# connectors.net
KiCad netlist of a schematic drawn in Altium Designer
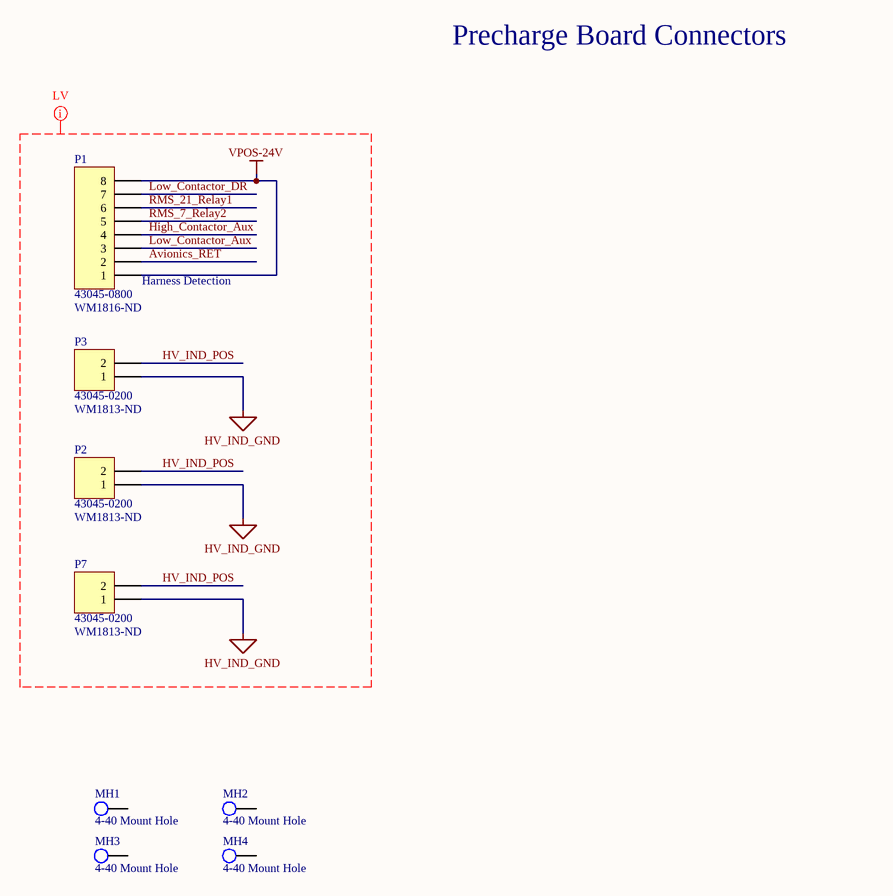
[diagram p0: connectors.SchDoc]

(export (version "E")
  (design (tool "Eeschema 10.0.6"))
  (components
    (comp (ref "MH1")
      (value "4-40 Mount Hole")
      (footprint "MH")
      (libsource (lib "misc") (part "4-40 Mount Hole"))
    )
    (comp (ref "MH2")
      (value "4-40 Mount Hole")
      (footprint "MH")
      (libsource (lib "misc") (part "4-40 Mount Hole"))
    )
    (comp (ref "MH3")
      (value "4-40 Mount Hole")
      (footprint "MH")
      (libsource (lib "misc") (part "4-40 Mount Hole"))
    )
    (comp (ref "MH4")
      (value "4-40 Mount Hole")
      (footprint "MH")
      (libsource (lib "misc") (part "4-40 Mount Hole"))
    )
    (comp (ref "P1")
      (value "43045-0800")
      (footprint "430450800")
      (description "CONN HEADER R/A 8POS 3MM")
      (fields (field (name "MANUFACTURER") "Molex") (field (name "SUPPLIER PART NUMBER 1") "WM1816-ND"))
      (libsource (lib "connector") (part "43045-0800"))
    )
    (comp (ref "P2")
      (value "43045-0200")
      (footprint "430450200")
      (description "CONN HEADER R/A 2POS")
      (fields (field (name "MANUFACTURER") "Molex") (field (name "SUPPLIER PART NUMBER 1") "WM1813-ND"))
      (libsource (lib "connector") (part "43045-0200"))
    )
    (comp (ref "P3")
      (value "43045-0200")
      (footprint "430450200")
      (description "CONN HEADER R/A 2POS")
      (fields (field (name "MANUFACTURER") "Molex") (field (name "SUPPLIER PART NUMBER 1") "WM1813-ND"))
      (libsource (lib "connector") (part "43045-0200"))
    )
    (comp (ref "P7")
      (value "43045-0200")
      (footprint "430450200")
      (description "CONN HEADER R/A 2POS")
      (fields (field (name "MANUFACTURER") "Molex") (field (name "SUPPLIER PART NUMBER 1") "WM1813-ND"))
      (libsource (lib "connector") (part "43045-0200"))
    )
  )
  (nets
    (net (code "1") (name "/Avionics_RET") (class "Default")
      (node (ref "P1") (pin "2") (pinfunction "2_2") (pintype "passive"))
    )
    (net (code "2") (name "/HV_IND_POS") (class "Default")
      (node (ref "P2") (pin "2") (pinfunction "2_2") (pintype "passive"))
      (node (ref "P3") (pin "2") (pinfunction "2_2") (pintype "passive"))
      (node (ref "P7") (pin "2") (pinfunction "2_2") (pintype "passive"))
    )
    (net (code "3") (name "/High_Contactor_Aux") (class "Default")
      (node (ref "P1") (pin "4") (pinfunction "4_4") (pintype "passive"))
    )
    (net (code "4") (name "/Low_Contactor_Aux") (class "Default")
      (node (ref "P1") (pin "3") (pinfunction "3_3") (pintype "passive"))
    )
    (net (code "5") (name "/Low_Contactor_DR") (class "Default")
      (node (ref "P1") (pin "7") (pinfunction "7_7") (pintype "passive"))
    )
    (net (code "6") (name "/RMS_7_Relay2") (class "Default")
      (node (ref "P1") (pin "5") (pinfunction "5_5") (pintype "passive"))
    )
    (net (code "7") (name "/RMS_21_Relay1") (class "Default")
      (node (ref "P1") (pin "6") (pinfunction "6_6") (pintype "passive"))
    )
    (net (code "8") (name "HV_IND_GND") (class "Default")
      (node (ref "P2") (pin "1") (pinfunction "1_1") (pintype "passive"))
      (node (ref "P3") (pin "1") (pinfunction "1_1") (pintype "passive"))
      (node (ref "P7") (pin "1") (pinfunction "1_1") (pintype "passive"))
    )
    (net (code "9") (name "VPOS-24V") (class "Default")
      (node (ref "P1") (pin "1") (pinfunction "1_1") (pintype "passive"))
      (node (ref "P1") (pin "8") (pinfunction "8_8") (pintype "passive"))
    )
    (net (code "10") (name "unconnected-(MH1-Pad46)") (class "Default")
      (node (ref "MH1") (pin "46") (pinfunction "46_46") (pintype "passive"))
    )
    (net (code "11") (name "unconnected-(MH2-Pad46)") (class "Default")
      (node (ref "MH2") (pin "46") (pinfunction "46_46") (pintype "passive"))
    )
    (net (code "12") (name "unconnected-(MH3-Pad46)") (class "Default")
      (node (ref "MH3") (pin "46") (pinfunction "46_46") (pintype "passive"))
    )
    (net (code "13") (name "unconnected-(MH4-Pad46)") (class "Default")
      (node (ref "MH4") (pin "46") (pinfunction "46_46") (pintype "passive"))
    )
  )
)
